# outputs-voltage-and-current-measurements.net
KiCad netlist of a schematic drawn in Altium Designer
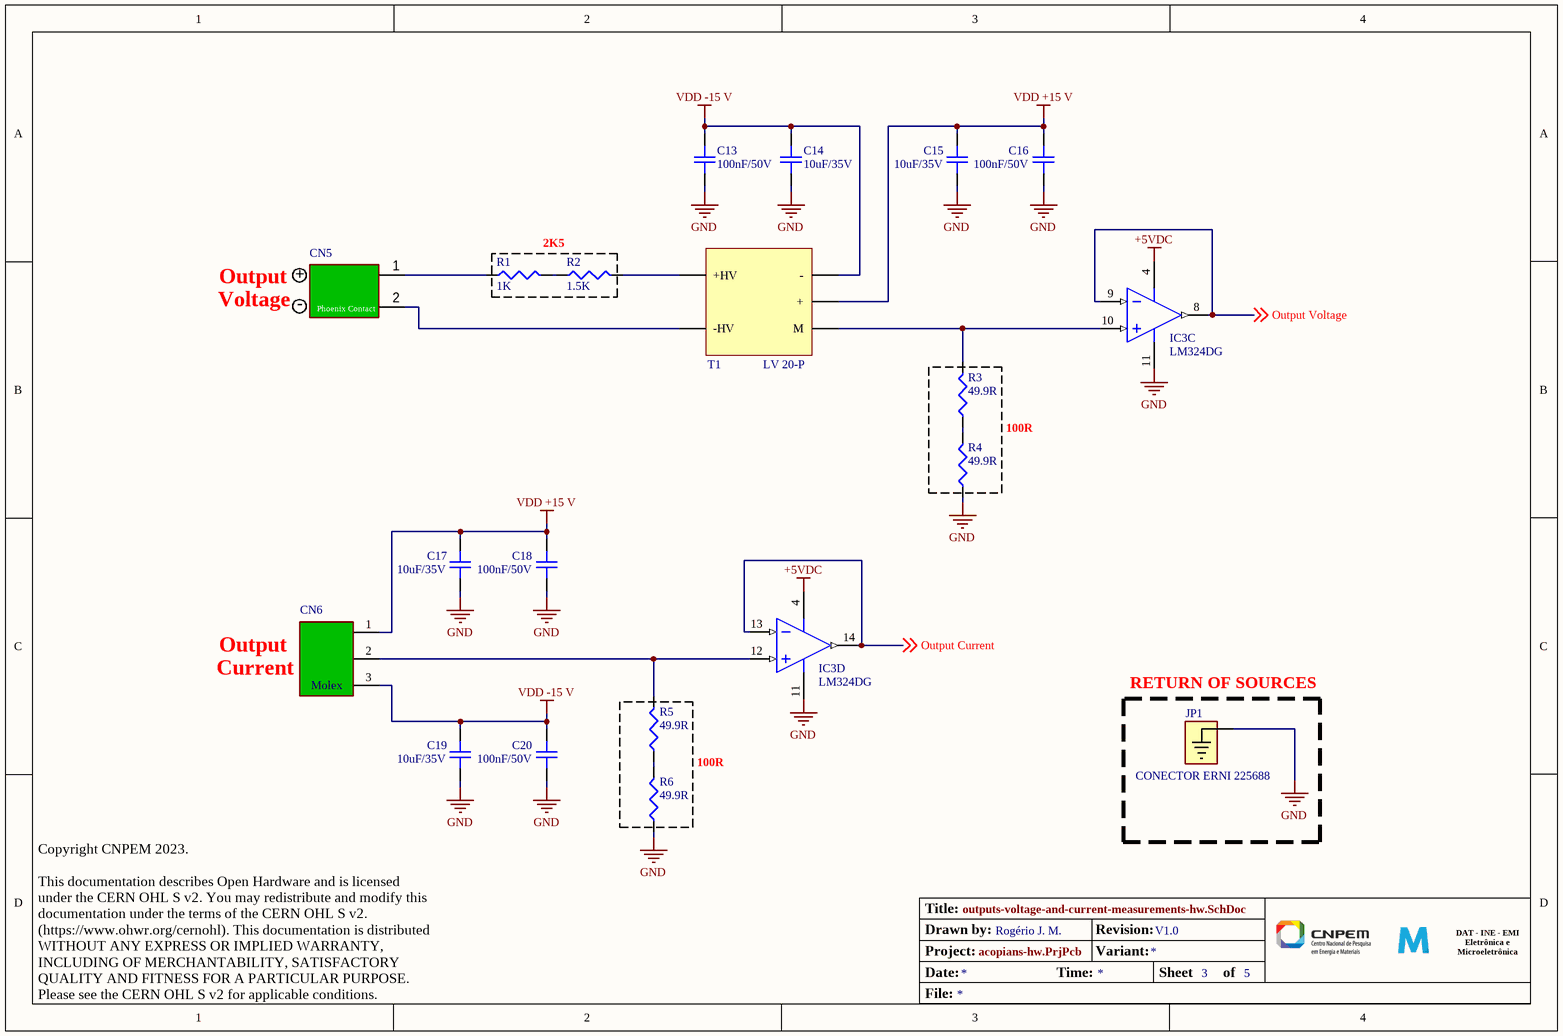
[diagram p0: outputs-voltage-and-current-measurements-hw.SchDoc]

(export (version "E")
  (design (tool "Eeschema 10.0.6"))
  (components
    (comp (ref "C13")
      (value "100nF/50V")
      (footprint "C0805")
      (description "Capacitor 0.1UF 50V X7R 0805")
      (fields (field (name "TOLERANCE") "10%") (field (name "VOLTAGE") "50V"))
      (libsource (lib "acopians-monitoring-hw-library-schematic") (part "CAPACITOR 100nF/50V"))
    )
    (comp (ref "C14")
      (value "10uF/35V")
      (footprint "C0805")
      (description "Capacitor 10UF 35V X5R 0805")
      (fields
        (field (name "MANUFACTURER") "TDK")
        (field (name "MANUFACTURER PART NUMBER") "C2012X5R1V106K085AC")
      )
      (libsource (lib "acopians-monitoring-hw-library-schematic") (part "CAPACITOR 10uF/35V"))
    )
    (comp (ref "C15")
      (value "10uF/35V")
      (footprint "C0805")
      (description "Capacitor 10UF 35V X5R 0805")
      (fields
        (field (name "MANUFACTURER") "TDK")
        (field (name "MANUFACTURER PART NUMBER") "C2012X5R1V106K085AC")
      )
      (libsource (lib "acopians-monitoring-hw-library-schematic") (part "CAPACITOR 10uF/35V"))
    )
    (comp (ref "C16")
      (value "100nF/50V")
      (footprint "C0805")
      (description "Capacitor 0.1UF 50V X7R 0805")
      (fields (field (name "TOLERANCE") "10%") (field (name "VOLTAGE") "50V"))
      (libsource (lib "acopians-monitoring-hw-library-schematic") (part "CAPACITOR 100nF/50V"))
    )
    (comp (ref "C17")
      (value "10uF/35V")
      (footprint "C0805")
      (description "Capacitor 10UF 35V X5R 0805")
      (fields
        (field (name "MANUFACTURER") "TDK")
        (field (name "MANUFACTURER PART NUMBER") "C2012X5R1V106K085AC")
      )
      (libsource (lib "acopians-monitoring-hw-library-schematic") (part "CAPACITOR 10uF/35V"))
    )
    (comp (ref "C18")
      (value "100nF/50V")
      (footprint "C0805")
      (description "Capacitor 0.1UF 50V X7R 0805")
      (fields (field (name "TOLERANCE") "10%") (field (name "VOLTAGE") "50V"))
      (libsource (lib "acopians-monitoring-hw-library-schematic") (part "CAPACITOR 100nF/50V"))
    )
    (comp (ref "C19")
      (value "10uF/35V")
      (footprint "C0805")
      (description "Capacitor 10UF 35V X5R 0805")
      (fields
        (field (name "MANUFACTURER") "TDK")
        (field (name "MANUFACTURER PART NUMBER") "C2012X5R1V106K085AC")
      )
      (libsource (lib "acopians-monitoring-hw-library-schematic") (part "CAPACITOR 10uF/35V"))
    )
    (comp (ref "C20")
      (value "100nF/50V")
      (footprint "C0805")
      (description "Capacitor 0.1UF 50V X7R 0805")
      (fields (field (name "TOLERANCE") "10%") (field (name "VOLTAGE") "50V"))
      (libsource (lib "acopians-monitoring-hw-library-schematic") (part "CAPACITOR 100nF/50V"))
    )
    (comp (ref "CN5")
      (value "1755736")
      (footprint "Conector Phoenix 2 vias 1755736")
      (description "Conector Phoenix 2 vias 1755736")
      (fields (field (name "MANUFACTURER") "Phoenix Contact"))
      (libsource (lib "acopians-monitoring-hw-library-schematic") (part "CONECTOR PHOENIX 2 VIAS 1755736"))
    )
    (comp (ref "CN6")
      (value "Header Molex 3 Pin 22-27-2031")
      (footprint "HEADER MOLEX 22 27 2031")
      (fields
        (field (name "MANUFACTURER") "Molex, LLC")
        (field (name "MANUFACTURER PART NUMBER") "0022272031")
      )
      (libsource (lib "acopians-monitoring-hw-library-schematic") (part "HEADER MOLEX 22-27-2031"))
    )
    (comp (ref "IC3")
      (value "LM324DG")
      (footprint "SOIC-14")
      (description "Operational Amplifiers - Op Amps 3-32V Quad 5mV")
      (libsource (lib "acopians-monitoring-hw-library-schematic") (part "LM324DG"))
    )
    (comp (ref "JP1")
      (value "CONECTOR ERNI 225688")
      (footprint "CONECTOR ERNI 225688")
      (description "Conector ERNI 225688")
      (libsource (lib "acopians-monitoring-hw-library-schematic") (part "CONECTOR ERNI 225688"))
    )
    (comp (ref "R1")
      (value "1K")
      (footprint "R0805")
      (description "Resistor SMD 1K OHM 0.1% 1/4W 0805")
      (fields (field (name "TOLERANCE") "0.1%"))
      (libsource (lib "acopians-monitoring-hw-library-schematic") (part "RESISTOR 1K"))
    )
    (comp (ref "R2")
      (value "1.5K")
      (footprint "R0603")
      (description "Resistor SMD 1.5K OHM 0.1% 1/10W 0603")
      (fields (field (name "TOLERANCE") "0.1%"))
      (libsource (lib "acopians-monitoring-hw-library-schematic") (part "RESISTOR 1.5K"))
    )
    (comp (ref "R3")
      (value "49.9R")
      (footprint "R0603")
      (description "Resistor SMD 49.9R OHM 0.1% 1/10W 0603")
      (fields (field (name "TOLERANCE") "0.1%"))
      (libsource (lib "acopians-monitoring-hw-library-schematic") (part "RESISTOR 49.9R"))
    )
    (comp (ref "R4")
      (value "49.9R")
      (footprint "R0603")
      (description "Resistor SMD 49.9R OHM 0.1% 1/10W 0603")
      (fields (field (name "TOLERANCE") "0.1%"))
      (libsource (lib "acopians-monitoring-hw-library-schematic") (part "RESISTOR 49.9R"))
    )
    (comp (ref "R5")
      (value "49.9R")
      (footprint "R0603")
      (description "Resistor SMD 49.9R OHM 0.1% 1/10W 0603")
      (fields (field (name "TOLERANCE") "0.1%"))
      (libsource (lib "acopians-monitoring-hw-library-schematic") (part "RESISTOR 49.9R"))
    )
    (comp (ref "R6")
      (value "49.9R")
      (footprint "R0603")
      (description "Resistor SMD 49.9R OHM 0.1% 1/10W 0603")
      (fields (field (name "TOLERANCE") "0.1%"))
      (libsource (lib "acopians-monitoring-hw-library-schematic") (part "RESISTOR 49.9R"))
    )
    (comp (ref "T1")
      (value "Voltagem Transducer LV 20-P")
      (footprint "VOLTAGE TRANSDUCER LV 20-P")
      (fields
        (field (name "MANUFACTURER") "LEM USA Inc.")
        (field (name "MANUFACTURER PART NUMBER") "LV 20-P")
        (field (name "TEXT") "LV 20-P")
      )
      (libsource (lib "acopians-monitoring-hw-library-schematic") (part "VOLTAGE TRANSDUCER LV 20-P"))
    )
  )
  (nets
    (net (code "1") (name "+5VDC") (class "Default")
      (node (ref "IC3") (pin "4") (pinfunction "V+_4") (pintype "power_in"))
    )
    (net (code "2") (name "GND") (class "Default")
      (node (ref "C13") (pin "1") (pinfunction "1_1") (pintype "passive"))
      (node (ref "C14") (pin "1") (pinfunction "1_1") (pintype "passive"))
      (node (ref "C15") (pin "1") (pinfunction "1_1") (pintype "passive"))
      (node (ref "C16") (pin "1") (pinfunction "1_1") (pintype "passive"))
      (node (ref "C17") (pin "1") (pinfunction "1_1") (pintype "passive"))
      (node (ref "C18") (pin "1") (pinfunction "1_1") (pintype "passive"))
      (node (ref "C19") (pin "1") (pinfunction "1_1") (pintype "passive"))
      (node (ref "C20") (pin "1") (pinfunction "1_1") (pintype "passive"))
      (node (ref "IC3") (pin "11") (pinfunction "V-_11") (pintype "power_in"))
      (node (ref "JP1") (pin "1") (pinfunction "1_1") (pintype "passive"))
      (node (ref "R4") (pin "1") (pinfunction "1_1") (pintype "passive"))
      (node (ref "R6") (pin "1") (pinfunction "1_1") (pintype "passive"))
    )
    (net (code "3") (name "Net-(CN5-Pad1)") (class "Default")
      (node (ref "CN5") (pin "1") (pinfunction "1_1") (pintype "passive"))
      (node (ref "R1") (pin "1") (pinfunction "1_1") (pintype "passive"))
    )
    (net (code "4") (name "Net-(CN6-M)") (class "Default")
      (node (ref "CN6") (pin "2") (pinfunction "M_2") (pintype "passive"))
      (node (ref "IC3") (pin "12") (pinfunction "IN_D+_12") (pintype "input"))
      (node (ref "R5") (pin "2") (pinfunction "2_2") (pintype "passive"))
    )
    (net (code "5") (name "Net-(IC3C-IN_C+)") (class "Default")
      (node (ref "IC3") (pin "10") (pinfunction "IN_C+_10") (pintype "input"))
      (node (ref "R3") (pin "2") (pinfunction "2_2") (pintype "passive"))
      (node (ref "T1") (pin "5") (pinfunction "M_5") (pintype "passive"))
    )
    (net (code "6") (name "Net-(R1-Pad2)") (class "Default")
      (node (ref "R1") (pin "2") (pinfunction "2_2") (pintype "passive"))
      (node (ref "R2") (pin "1") (pinfunction "1_1") (pintype "passive"))
    )
    (net (code "7") (name "Net-(R3-Pad1)") (class "Default")
      (node (ref "R3") (pin "1") (pinfunction "1_1") (pintype "passive"))
      (node (ref "R4") (pin "2") (pinfunction "2_2") (pintype "passive"))
    )
    (net (code "8") (name "Net-(R5-Pad1)") (class "Default")
      (node (ref "R5") (pin "1") (pinfunction "1_1") (pintype "passive"))
      (node (ref "R6") (pin "2") (pinfunction "2_2") (pintype "passive"))
    )
    (net (code "9") (name "Net-(T1-+HV)") (class "Default")
      (node (ref "R2") (pin "2") (pinfunction "2_2") (pintype "passive"))
      (node (ref "T1") (pin "1") (pinfunction "+HV_1") (pintype "passive"))
    )
    (net (code "10") (name "Net-(T1--HV)") (class "Default")
      (node (ref "CN5") (pin "2") (pinfunction "2_2") (pintype "passive"))
      (node (ref "T1") (pin "2") (pinfunction "-HV_2") (pintype "passive"))
    )
    (net (code "11") (name "Output Current") (class "Default")
      (node (ref "IC3") (pin "13") (pinfunction "IN_D-_13") (pintype "input"))
      (node (ref "IC3") (pin "14") (pinfunction "OUT_D_14") (pintype "output"))
    )
    (net (code "12") (name "Output Voltage") (class "Default")
      (node (ref "IC3") (pin "8") (pinfunction "OUT_C_8") (pintype "output"))
      (node (ref "IC3") (pin "9") (pinfunction "IN_C-_9") (pintype "input"))
    )
    (net (code "13") (name "VDD +15 V") (class "Default")
      (node (ref "C15") (pin "2") (pinfunction "2_2") (pintype "passive"))
      (node (ref "C16") (pin "2") (pinfunction "2_2") (pintype "passive"))
      (node (ref "C17") (pin "2") (pinfunction "2_2") (pintype "passive"))
      (node (ref "C18") (pin "2") (pinfunction "2_2") (pintype "passive"))
      (node (ref "CN6") (pin "1") (pinfunction "+15V_1") (pintype "passive"))
      (node (ref "T1") (pin "4") (pinfunction "+_4") (pintype "passive"))
    )
    (net (code "14") (name "VDD -15 V") (class "Default")
      (node (ref "C13") (pin "2") (pinfunction "2_2") (pintype "passive"))
      (node (ref "C14") (pin "2") (pinfunction "2_2") (pintype "passive"))
      (node (ref "C19") (pin "2") (pinfunction "2_2") (pintype "passive"))
      (node (ref "C20") (pin "2") (pinfunction "2_2") (pintype "passive"))
      (node (ref "CN6") (pin "3") (pinfunction "-15V_3") (pintype "passive"))
      (node (ref "T1") (pin "3") (pinfunction "-_3") (pintype "passive"))
    )
  )
)
